# ESP32_Schematic_Sheet.net
KiCad netlist of a schematic drawn in Altium Designer
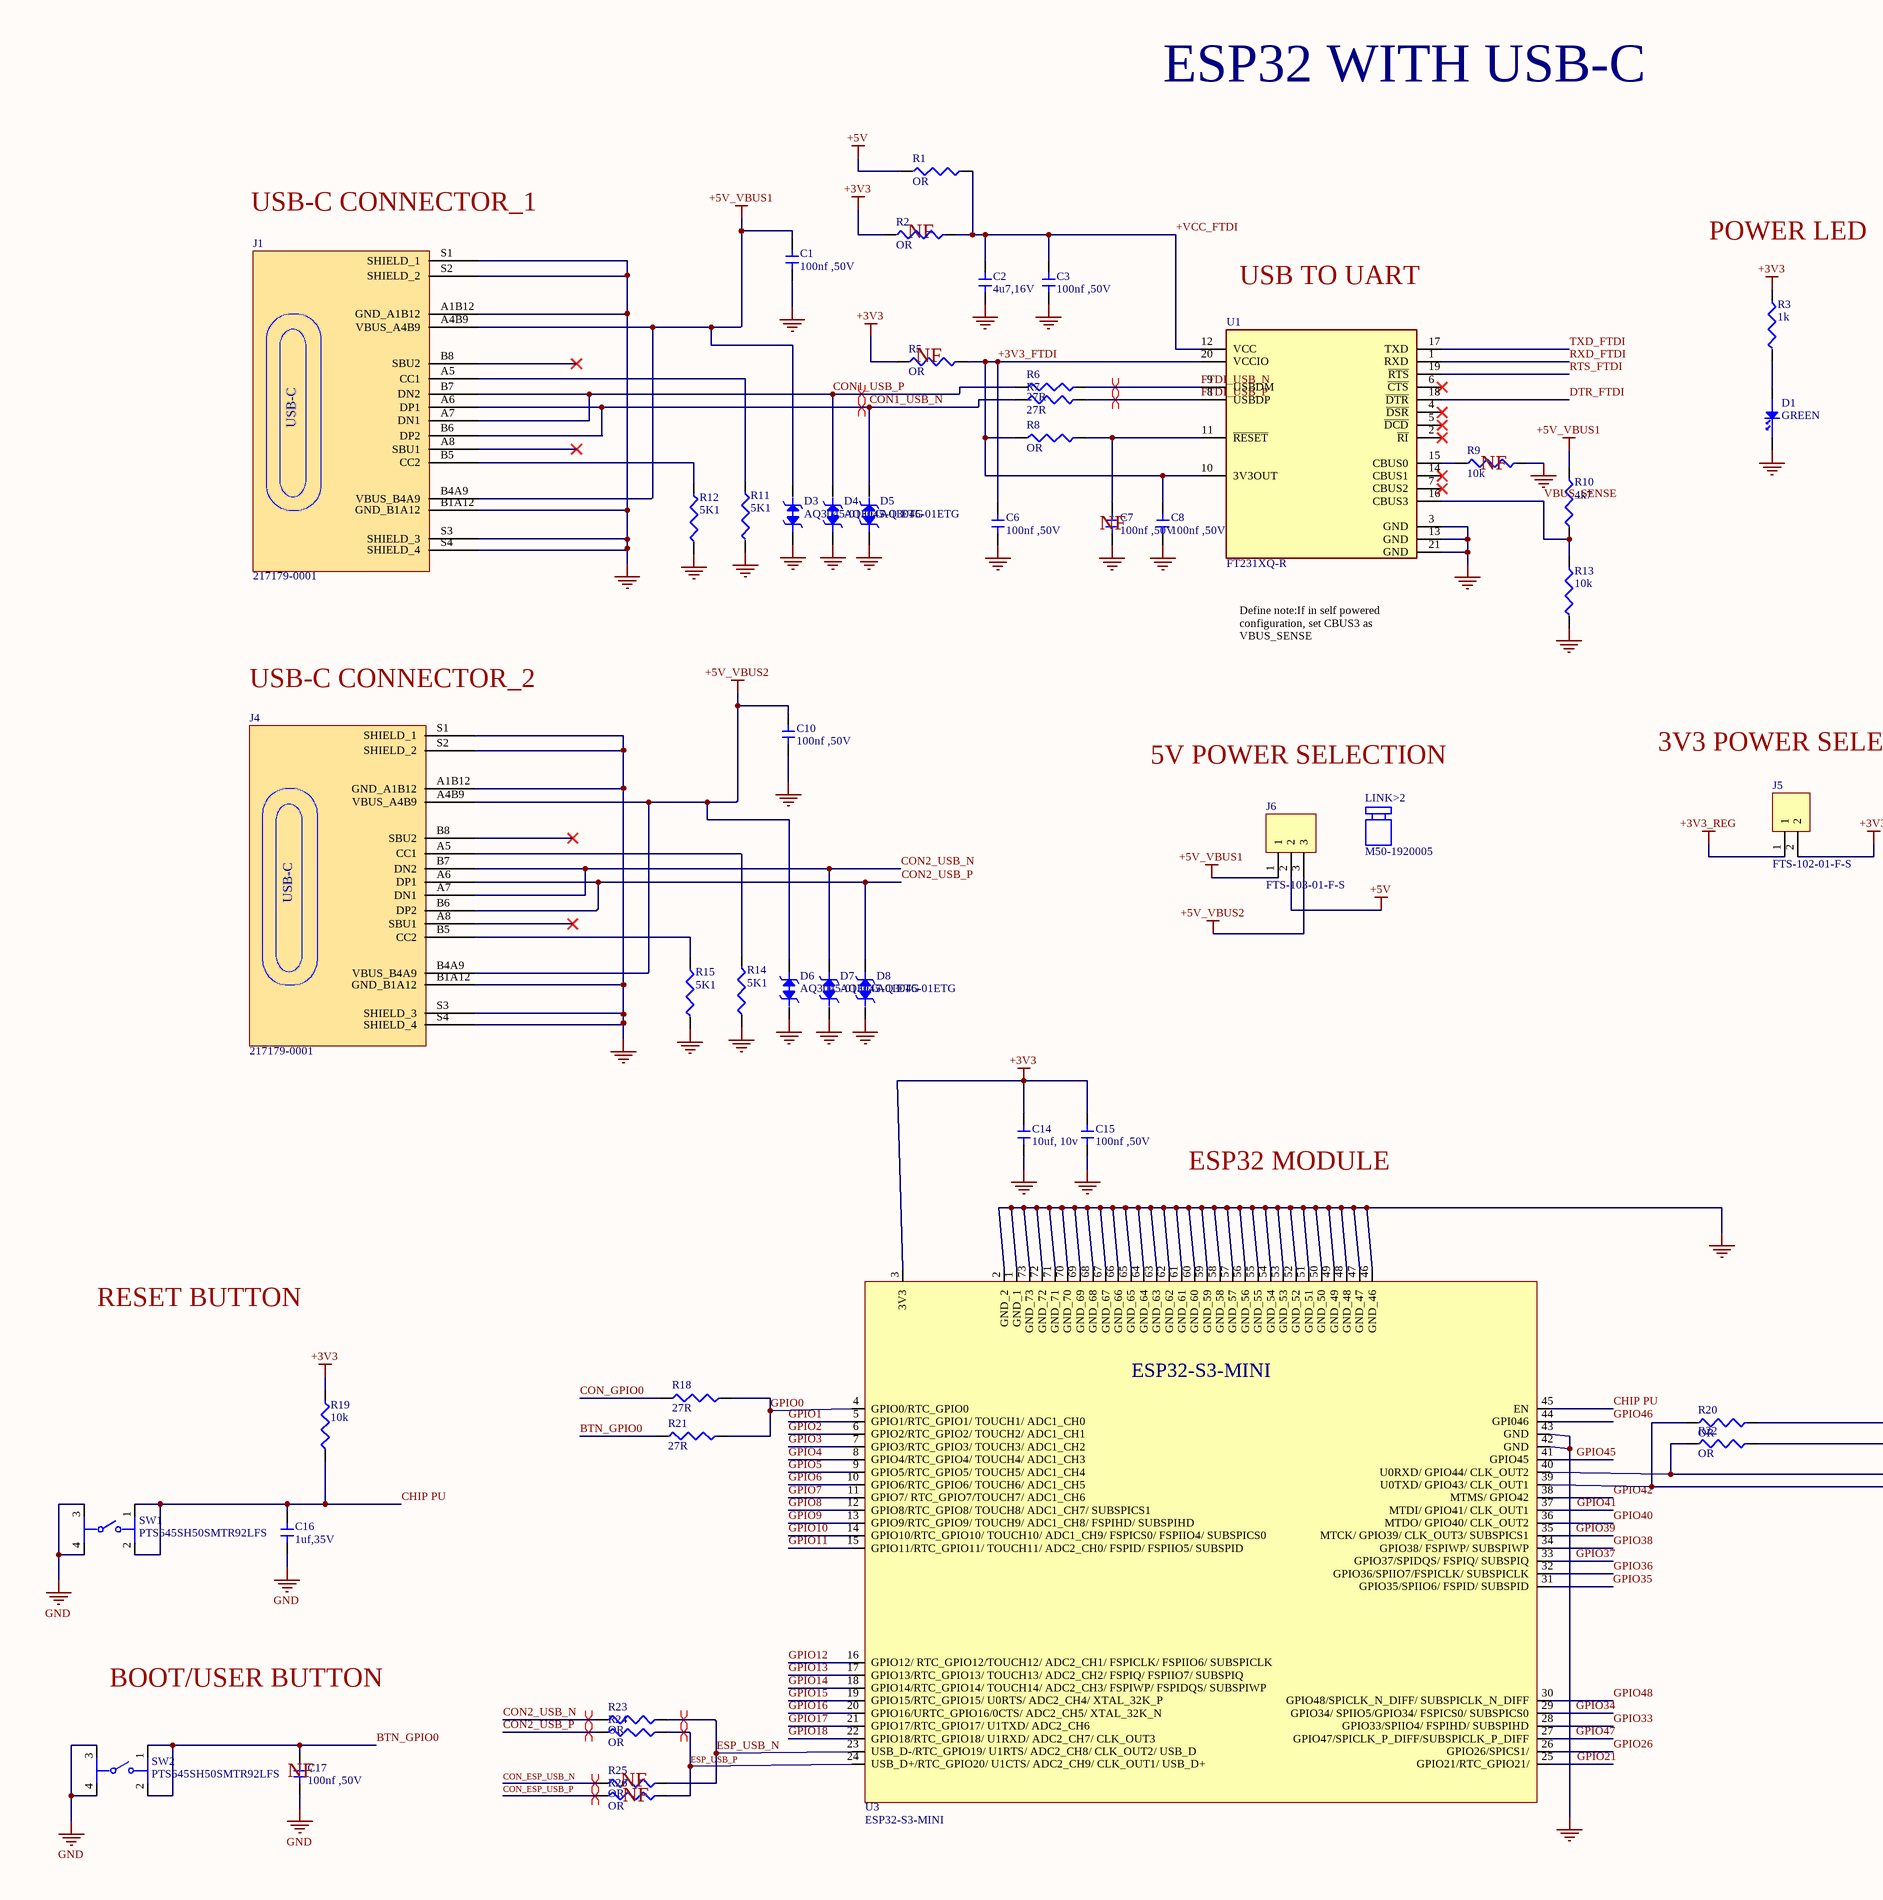
[diagram p0: ESP32 Schematic Sheet.SchDoc, left]
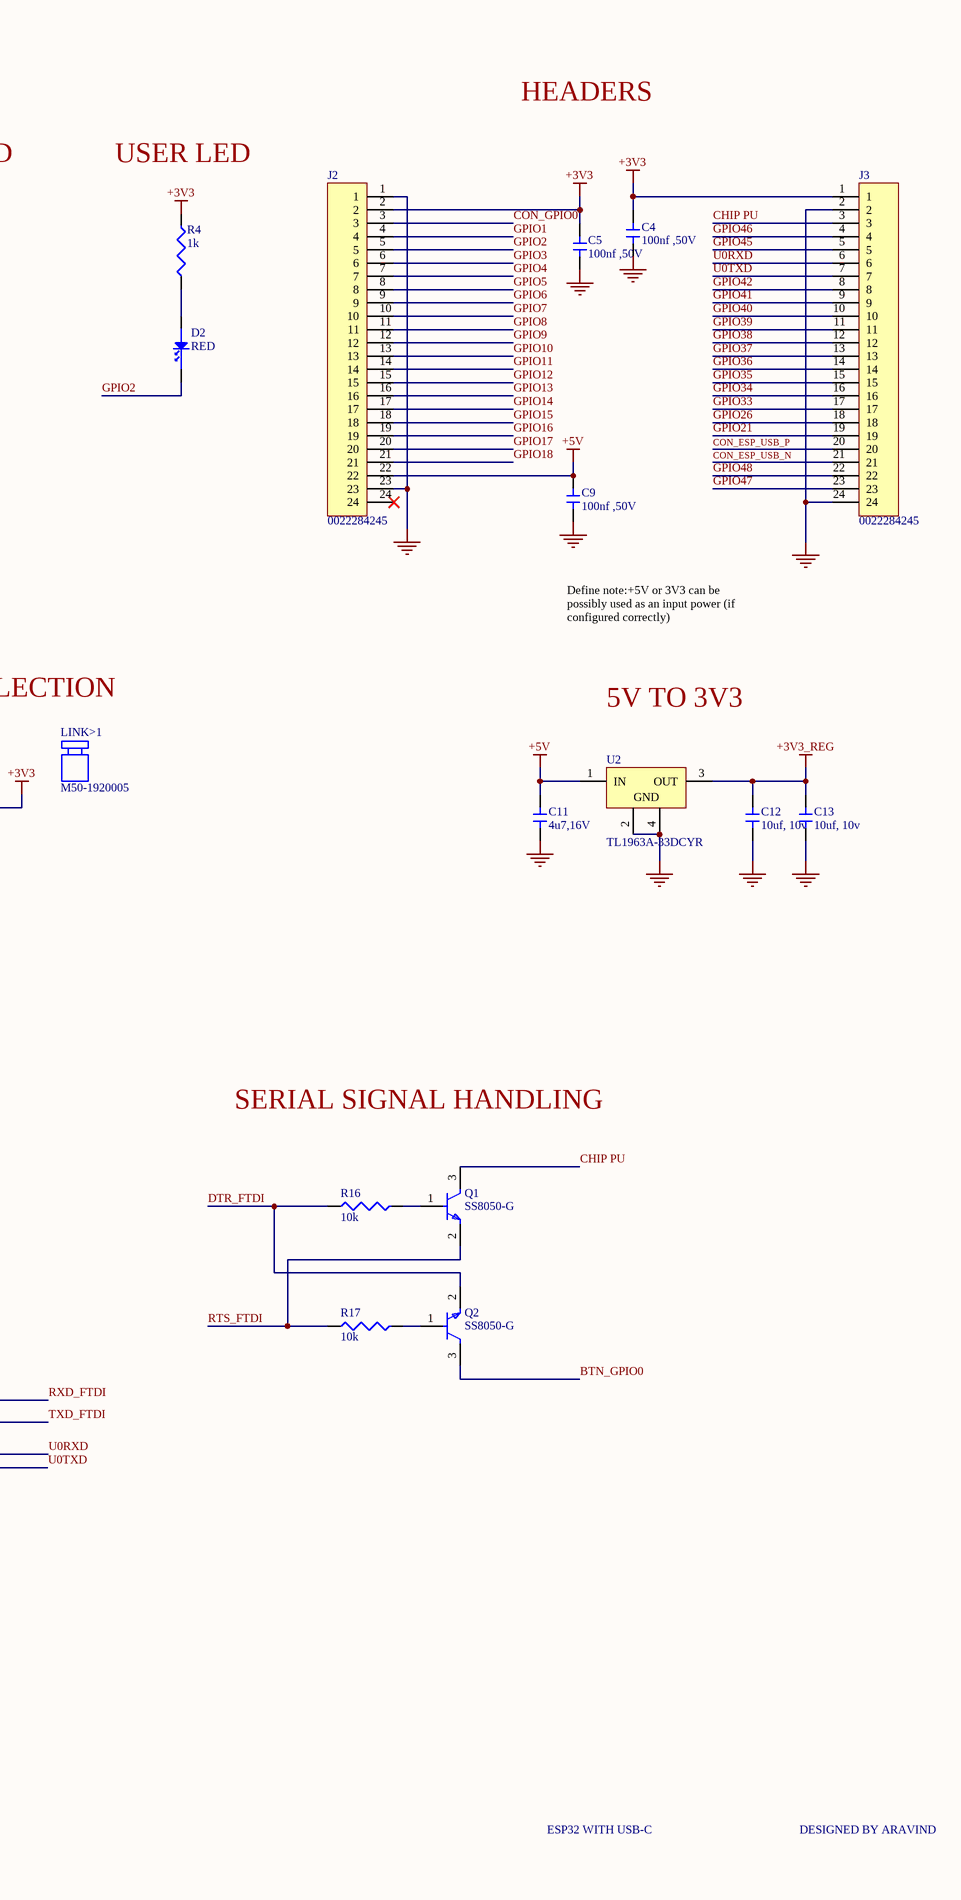
[diagram p1: ESP32 Schematic Sheet.SchDoc, right]

(export (version "E")
  (design (tool "Eeschema 10.0.6"))
  (components
    (comp (ref "C1")
      (value "100nf ,50V")
      (footprint "CAPC1005X55N")
      (description "CAP CER 0.1UF 50V X7R 0402")
      (fields
        (field (name "MANUFACTURER") "Samsung Electro-Mechanics")
        (field (name "MANUFACTURER PART NUMBER") "CL05B104KB5NNNC")
      )
      (libsource (lib "Schlib1") (part "CL05B104KB5NNNC"))
    )
    (comp (ref "C2")
      (value "4u7,16V")
      (footprint "CAPC1005X55N")
      (description "CAP CER 4.7UF 16V X5R 0402")
      (fields
        (field (name "MANUFACTURER") "Samsung Electro-Mechanics")
        (field (name "MANUFACTURER PART NUMBER") "CL05A475MO5NUNC")
      )
      (libsource (lib "Schlib1") (part "CL05A475MO5NUNC"))
    )
    (comp (ref "C3")
      (value "100nf ,50V")
      (footprint "CAPC1005X55N")
      (description "CAP CER 0.1UF 50V X7R 0402")
      (fields
        (field (name "MANUFACTURER") "Samsung Electro-Mechanics")
        (field (name "MANUFACTURER PART NUMBER") "CL05B104KB5NNNC")
      )
      (libsource (lib "Schlib1") (part "CL05B104KB5NNNC"))
    )
    (comp (ref "C4")
      (value "100nf ,50V")
      (footprint "CAPC1005X55N")
      (description "CAP CER 0.1UF 50V X7R 0402")
      (fields
        (field (name "MANUFACTURER") "Samsung Electro-Mechanics")
        (field (name "MANUFACTURER PART NUMBER") "CL05B104KB5NNNC")
      )
      (libsource (lib "Schlib1") (part "CL05B104KB5NNNC"))
    )
    (comp (ref "C5")
      (value "100nf ,50V")
      (footprint "CAPC1005X55N")
      (description "CAP CER 0.1UF 50V X7R 0402")
      (fields
        (field (name "MANUFACTURER") "Samsung Electro-Mechanics")
        (field (name "MANUFACTURER PART NUMBER") "CL05B104KB5NNNC")
      )
      (libsource (lib "Schlib1") (part "CL05B104KB5NNNC"))
    )
    (comp (ref "C6")
      (value "100nf ,50V")
      (footprint "CAPC1005X55N")
      (description "CAP CER 0.1UF 50V X7R 0402")
      (fields
        (field (name "MANUFACTURER") "Samsung Electro-Mechanics")
        (field (name "MANUFACTURER PART NUMBER") "CL05B104KB5NNNC")
      )
      (libsource (lib "Schlib1") (part "CL05B104KB5NNNC"))
    )
    (comp (ref "C7")
      (value "100nf ,50V")
      (footprint "CAPC1005X55N")
      (description "CAP CER 0.1UF 50V X7R 0402")
      (fields
        (field (name "MANUFACTURER") "Samsung Electro-Mechanics")
        (field (name "MANUFACTURER PART NUMBER") "CL05B104KB5NNNC")
      )
      (libsource (lib "Schlib1") (part "CL05B104KB5NNNC"))
    )
    (comp (ref "C8")
      (value "100nf ,50V")
      (footprint "CAPC1005X55N")
      (description "CAP CER 0.1UF 50V X7R 0402")
      (fields
        (field (name "MANUFACTURER") "Samsung Electro-Mechanics")
        (field (name "MANUFACTURER PART NUMBER") "CL05B104KB5NNNC")
      )
      (libsource (lib "Schlib1") (part "CL05B104KB5NNNC"))
    )
    (comp (ref "C9")
      (value "100nf ,50V")
      (footprint "CAPC1005X55N")
      (description "CAP CER 0.1UF 50V X7R 0402")
      (fields
        (field (name "MANUFACTURER") "Samsung Electro-Mechanics")
        (field (name "MANUFACTURER PART NUMBER") "CL05B104KB5NNNC")
      )
      (libsource (lib "Schlib1") (part "CL05B104KB5NNNC"))
    )
    (comp (ref "C10")
      (value "100nf ,50V")
      (footprint "CAPC1005X55N")
      (description "CAP CER 0.1UF 50V X7R 0402")
      (fields
        (field (name "MANUFACTURER") "Samsung Electro-Mechanics")
        (field (name "MANUFACTURER PART NUMBER") "CL05B104KB5NNNC")
      )
      (libsource (lib "Schlib1") (part "CL05B104KB5NNNC"))
    )
    (comp (ref "C11")
      (value "4u7,16V")
      (footprint "CAPC1005X55N")
      (description "CAP CER 4.7UF 16V X5R 0402")
      (fields
        (field (name "MANUFACTURER") "Samsung Electro-Mechanics")
        (field (name "MANUFACTURER PART NUMBER") "CL05A475MO5NUNC")
      )
      (libsource (lib "Schlib1") (part "CL05A475MO5NUNC"))
    )
    (comp (ref "C12")
      (value "10uf, 10v")
      (footprint "CAPC1005X55N")
      (description "CAP CER 10UF 10V X5R 0402")
      (fields
        (field (name "MANUFACTURER") "Samsung Electro-Mechanics")
        (field (name "MANUFACTURER PART NUMBER") "CL05A106MP8NUB8")
      )
      (libsource (lib "Schlib1") (part "CL05A106MP8NUB8"))
    )
    (comp (ref "C13")
      (value "10uf, 10v")
      (footprint "CAPC1005X55N")
      (description "CAP CER 10UF 10V X5R 0402")
      (fields
        (field (name "MANUFACTURER") "Samsung Electro-Mechanics")
        (field (name "MANUFACTURER PART NUMBER") "CL05A106MP8NUB8")
      )
      (libsource (lib "Schlib1") (part "CL05A106MP8NUB8"))
    )
    (comp (ref "C14")
      (value "10uf, 10v")
      (footprint "CAPC1005X55N")
      (description "CAP CER 10UF 10V X5R 0402")
      (fields
        (field (name "MANUFACTURER") "Samsung Electro-Mechanics")
        (field (name "MANUFACTURER PART NUMBER") "CL05A106MP8NUB8")
      )
      (libsource (lib "Schlib1") (part "CL05A106MP8NUB8"))
    )
    (comp (ref "C15")
      (value "100nf ,50V")
      (footprint "CAPC1005X55N")
      (description "CAP CER 0.1UF 50V X7R 0402")
      (fields
        (field (name "MANUFACTURER") "Samsung Electro-Mechanics")
        (field (name "MANUFACTURER PART NUMBER") "CL05B104KB5NNNC")
      )
      (libsource (lib "Schlib1") (part "CL05B104KB5NNNC"))
    )
    (comp (ref "C16")
      (value "1uf,35V")
      (footprint "CAPC1005X55N")
      (description "CAP CER 1UF 35V X5R 0402")
      (fields
        (field (name "MANUFACTURER") "Samsung Electro-Mechanics")
        (field (name "MANUFACTURER PART NUMBER") "CL05A105KL5NRNC")
      )
      (libsource (lib "Schlib1") (part "CL05A105KL5NRNC"))
    )
    (comp (ref "C17")
      (value "100nf ,50V")
      (footprint "CAPC1005X55N")
      (description "CAP CER 0.1UF 50V X7R 0402")
      (fields
        (field (name "MANUFACTURER") "Samsung Electro-Mechanics")
        (field (name "MANUFACTURER PART NUMBER") "CL05B104KB5NNNC")
      )
      (libsource (lib "Schlib1") (part "CL05B104KB5NNNC"))
    )
    (comp (ref "D1")
      (value "GREEN")
      (footprint "LED0402G")
      (description "LED YLW-GRN 0402 SMD")
      (fields
        (field (name "MANUFACTURER") "Vishay")
        (field (name "MANUFACTURER PART NUMBER") "VLMG1500-GS08")
      )
      (libsource (lib "Schlib1") (part "VLMG1500-GS08"))
    )
    (comp (ref "D2")
      (value "RED")
      (footprint "LED0402R")
      (description "LED RED 0402 SMD")
      (fields
        (field (name "MANUFACTURER") "Vishay")
        (field (name "MANUFACTURER PART NUMBER") "VLMS1500-GS08")
      )
      (libsource (lib "Schlib1") (part "VLMS1500-GS08"))
    )
    (comp (ref "D3")
      (value "AQ3045-01ETG")
      (footprint "SOD882")
      (description "TVS DIODE 5.3VWM 12VC SOD882")
      (fields (field (name "MANUFACTURER") "Littelfuse"))
      (libsource (lib "Schlib1") (part "AQ3045-01ETG"))
    )
    (comp (ref "D4")
      (value "AQ3045-01ETG")
      (footprint "SOD882")
      (description "TVS DIODE 5.3VWM 12VC SOD882")
      (fields (field (name "MANUFACTURER") "Littelfuse"))
      (libsource (lib "Schlib1") (part "AQ3045-01ETG"))
    )
    (comp (ref "D5")
      (value "AQ3045-01ETG")
      (footprint "SOD882")
      (description "TVS DIODE 5.3VWM 12VC SOD882")
      (fields (field (name "MANUFACTURER") "Littelfuse"))
      (libsource (lib "Schlib1") (part "AQ3045-01ETG"))
    )
    (comp (ref "D6")
      (value "AQ3045-01ETG")
      (footprint "SOD882")
      (description "TVS DIODE 5.3VWM 12VC SOD882")
      (fields (field (name "MANUFACTURER") "Littelfuse"))
      (libsource (lib "Schlib1") (part "AQ3045-01ETG"))
    )
    (comp (ref "D7")
      (value "AQ3045-01ETG")
      (footprint "SOD882")
      (description "TVS DIODE 5.3VWM 12VC SOD882")
      (fields (field (name "MANUFACTURER") "Littelfuse"))
      (libsource (lib "Schlib1") (part "AQ3045-01ETG"))
    )
    (comp (ref "D8")
      (value "AQ3045-01ETG")
      (footprint "SOD882")
      (description "TVS DIODE 5.3VWM 12VC SOD882")
      (fields (field (name "MANUFACTURER") "Littelfuse"))
      (libsource (lib "Schlib1") (part "AQ3045-01ETG"))
    )
    (comp (ref "J1")
      (value "217179-0001")
      (footprint "FP-2171790001-MFG")
      (description "CONN RCP USB2.0 TYP C 24P SMD RA")
      (fields (field (name "MANUFACTURER") "Molex"))
      (libsource (lib "Schlib1") (part "217179-0001"))
    )
    (comp (ref "J2")
      (value "0022284245")
      (footprint "HDR_1X24_2.54MM")
      (description "CONN HEADER VERT 24POS 2.54MM")
      (fields (field (name "MANUFACTURER") "Molex") (field (name "MANUFACTURER PART NUMBER") "22-28-4245"))
      (libsource (lib "Schlib1") (part "0022284245"))
    )
    (comp (ref "J3")
      (value "0022284245")
      (footprint "HDR_1X24_2.54MM")
      (description "CONN HEADER VERT 24POS 2.54MM")
      (fields (field (name "MANUFACTURER") "Molex") (field (name "MANUFACTURER PART NUMBER") "22-28-4245"))
      (libsource (lib "") (part "0022284245_1"))
    )
    (comp (ref "J4")
      (value "217179-0001")
      (footprint "FP-2171790001-MFG")
      (description "CONN RCP USB2.0 TYP C 24P SMD RA")
      (fields (field (name "MANUFACTURER") "Molex"))
      (libsource (lib "Schlib1") (part "217179-0001"))
    )
    (comp (ref "J5")
      (value "FTS-102-01-F-S")
      (footprint "HDR_1X2_1.27MM")
      (description "CONN HEADER VERT 2POS 1.27MM")
      (fields (field (name "MANUFACTURER") "Samtec"))
      (libsource (lib "FINALSchlib2") (part "FTS-102-01-F-S"))
    )
    (comp (ref "J6")
      (value "FTS-103-01-F-S")
      (footprint "HDR_1X3_1.27MM")
      (description "CONN HEADER VERT 3POS 1.27MM")
      (fields (field (name "MANUFACTURER") "Samtec"))
      (libsource (lib "Schlib1") (part "FTS-103-01-F-S"))
    )
    (comp (ref "LINK>1")
      (value "M50-1920005")
      (description "CONN SHUNT 1.27MM RED")
      (fields (field (name "MANUFACTURER") "Harwin"))
      (libsource (lib "Schlib1") (part "M50-1920005"))
    )
    (comp (ref "LINK>2")
      (value "M50-1920005")
      (description "CONN SHUNT 1.27MM RED")
      (fields (field (name "MANUFACTURER") "Harwin"))
      (libsource (lib "Schlib1") (part "M50-1920005"))
    )
    (comp (ref "Q1")
      (value "SS8050-G")
      (footprint "FP-SS8050-G-IPC_B")
      (description "TRANS NPN 25V 1.5A SOT-23-3")
      (fields (field (name "MANUFACTURER") "Comchip"))
      (libsource (lib "Schlib1") (part "SS8050-G"))
    )
    (comp (ref "Q2")
      (value "SS8050-G")
      (footprint "FP-SS8050-G-IPC_B")
      (description "TRANS NPN 25V 1.5A SOT-23-3")
      (fields (field (name "MANUFACTURER") "Comchip"))
      (libsource (lib "Schlib1") (part "SS8050-G"))
    )
    (comp (ref "R1")
      (value "OR")
      (footprint "RESC1005X37N")
      (description "RES 0 OHM JUMPER 1/16W 0402")
      (fields
        (field (name "MANUFACTURER") "Yageo Group")
        (field (name "MANUFACTURER PART NUMBER") "RC0402JR-070RL")
      )
      (libsource (lib "FINALSchlib2") (part "RC0402JR-070RL"))
    )
    (comp (ref "R2")
      (value "OR")
      (footprint "RESC1005X37N")
      (description "RES 0 OHM JUMPER 1/16W 0402")
      (fields
        (field (name "MANUFACTURER") "Yageo Group")
        (field (name "MANUFACTURER PART NUMBER") "RC0402JR-070RL")
      )
      (libsource (lib "FINALSchlib2") (part "RC0402JR-070RL"))
    )
    (comp (ref "R3")
      (value "1k")
      (footprint "RESC1005X37N")
      (description "RES 1K OHM 1% 1/16W 0402")
      (fields
        (field (name "MANUFACTURER") "Yageo Group")
        (field (name "MANUFACTURER PART NUMBER") "RC0402FR-071KL")
      )
      (libsource (lib "Schlib1") (part "RC0402FR-071KL"))
    )
    (comp (ref "R4")
      (value "1k")
      (footprint "RESC1005X37N")
      (description "RES 1K OHM 1% 1/16W 0402")
      (fields
        (field (name "MANUFACTURER") "Yageo Group")
        (field (name "MANUFACTURER PART NUMBER") "RC0402FR-071KL")
      )
      (libsource (lib "Schlib1") (part "RC0402FR-071KL"))
    )
    (comp (ref "R5")
      (value "OR")
      (footprint "RESC1005X37N")
      (description "RES 0 OHM JUMPER 1/16W 0402")
      (fields
        (field (name "MANUFACTURER") "TE Connectivity")
        (field (name "MANUFACTURER PART NUMBER") "CRG0402ZR")
      )
      (libsource (lib "Schlib1") (part "CRG0402ZR"))
    )
    (comp (ref "R6")
      (value "27R")
      (footprint "RESC1005X37N")
      (description "RES 27 OHM 1% 1/16W 0402")
      (fields
        (field (name "MANUFACTURER") "Yageo Group")
        (field (name "MANUFACTURER PART NUMBER") "RC0402FR-0727RL")
      )
      (libsource (lib "Schlib1") (part "RC0402FR-0727RL"))
    )
    (comp (ref "R7")
      (value "27R")
      (footprint "RESC1005X37N")
      (description "RES 27 OHM 1% 1/16W 0402")
      (fields
        (field (name "MANUFACTURER") "Yageo Group")
        (field (name "MANUFACTURER PART NUMBER") "RC0402FR-0727RL")
      )
      (libsource (lib "Schlib1") (part "RC0402FR-0727RL"))
    )
    (comp (ref "R8")
      (value "OR")
      (footprint "RESC1005X37N")
      (description "RES 0 OHM JUMPER 1/16W 0402")
      (fields
        (field (name "MANUFACTURER") "Yageo Group")
        (field (name "MANUFACTURER PART NUMBER") "RC0402JR-070RL")
      )
      (libsource (lib "FINALSchlib2") (part "RC0402JR-070RL"))
    )
    (comp (ref "R9")
      (value "10k")
      (footprint "RESC1005X37N")
      (description "RES SMD 10K OHM 1% 1/16W 0402")
      (fields
        (field (name "MANUFACTURER") "Yageo Group")
        (field (name "MANUFACTURER PART NUMBER") "AC0402FR-0710KL")
      )
      (libsource (lib "Schlib2") (part "AC0402FR-0710KL"))
    )
    (comp (ref "R10")
      (value "4k7")
      (footprint "RESC1005X37N")
      (description "RES 4.7K OHM 1% 1/16W 0402")
      (fields
        (field (name "MANUFACTURER") "Yageo Group")
        (field (name "MANUFACTURER PART NUMBER") "RC0402FR-074K7L")
      )
      (libsource (lib "Schlib1") (part "RC0402FR-074K7L"))
    )
    (comp (ref "R11")
      (value "5K1")
      (footprint "RESC1005X37N")
      (description "RES SMD 5.1K OHM 1% 1/16W 0402")
      (fields
        (field (name "MANUFACTURER") "Yageo Group")
        (field (name "MANUFACTURER PART NUMBER") "AC0402FR-075K1L")
      )
      (libsource (lib "Schlib1") (part "AC0402FR-075K1L"))
    )
    (comp (ref "R12")
      (value "5K1")
      (footprint "RESC1005X37N")
      (description "RES SMD 5.1K OHM 1% 1/16W 0402")
      (fields
        (field (name "MANUFACTURER") "Yageo Group")
        (field (name "MANUFACTURER PART NUMBER") "AC0402FR-075K1L")
      )
      (libsource (lib "Schlib1") (part "AC0402FR-075K1L"))
    )
    (comp (ref "R13")
      (value "10k")
      (footprint "RESC1005X37N")
      (description "RES SMD 10K OHM 1% 1/16W 0402")
      (fields
        (field (name "MANUFACTURER") "Yageo Group")
        (field (name "MANUFACTURER PART NUMBER") "AC0402FR-0710KL")
      )
      (libsource (lib "Schlib2") (part "AC0402FR-0710KL"))
    )
    (comp (ref "R14")
      (value "5K1")
      (footprint "RESC1005X37N")
      (description "RES SMD 5.1K OHM 1% 1/16W 0402")
      (fields
        (field (name "MANUFACTURER") "Yageo Group")
        (field (name "MANUFACTURER PART NUMBER") "AC0402FR-075K1L")
      )
      (libsource (lib "Schlib1") (part "AC0402FR-075K1L"))
    )
    (comp (ref "R15")
      (value "5K1")
      (footprint "RESC1005X37N")
      (description "RES SMD 5.1K OHM 1% 1/16W 0402")
      (fields
        (field (name "MANUFACTURER") "Yageo Group")
        (field (name "MANUFACTURER PART NUMBER") "AC0402FR-075K1L")
      )
      (libsource (lib "Schlib1") (part "AC0402FR-075K1L"))
    )
    (comp (ref "R16")
      (value "10k")
      (footprint "RESC1005X37N")
      (description "RES SMD 10K OHM 1% 1/16W 0402")
      (fields
        (field (name "MANUFACTURER") "Yageo Group")
        (field (name "MANUFACTURER PART NUMBER") "AC0402FR-0710KL")
      )
      (libsource (lib "Schlib2") (part "AC0402FR-0710KL"))
    )
    (comp (ref "R17")
      (value "10k")
      (footprint "RESC1005X37N")
      (description "RES SMD 10K OHM 1% 1/16W 0402")
      (fields
        (field (name "MANUFACTURER") "Yageo Group")
        (field (name "MANUFACTURER PART NUMBER") "AC0402FR-0710KL")
      )
      (libsource (lib "Schlib2") (part "AC0402FR-0710KL"))
    )
    (comp (ref "R18")
      (value "27R")
      (footprint "RESC1005X37N")
      (description "RES 27 OHM 1% 1/16W 0402")
      (fields
        (field (name "MANUFACTURER") "Yageo Group")
        (field (name "MANUFACTURER PART NUMBER") "RC0402FR-0727RL")
      )
      (libsource (lib "Schlib1") (part "RC0402FR-0727RL"))
    )
    (comp (ref "R19")
      (value "10k")
      (footprint "RESC1005X37N")
      (description "RES SMD 10K OHM 1% 1/16W 0402")
      (fields
        (field (name "MANUFACTURER") "Yageo Group")
        (field (name "MANUFACTURER PART NUMBER") "AC0402FR-0710KL")
      )
      (libsource (lib "Schlib2") (part "AC0402FR-0710KL"))
    )
    (comp (ref "R20")
      (value "OR")
      (footprint "RESC1005X37N")
      (description "RES 0 OHM JUMPER 1/16W 0402")
      (fields
        (field (name "MANUFACTURER") "Yageo Group")
        (field (name "MANUFACTURER PART NUMBER") "RC0402JR-070RL")
      )
      (libsource (lib "FINALSchlib2") (part "RC0402JR-070RL"))
    )
    (comp (ref "R21")
      (value "27R")
      (footprint "RESC1005X37N")
      (description "RES 27 OHM 1% 1/16W 0402")
      (fields
        (field (name "MANUFACTURER") "Yageo Group")
        (field (name "MANUFACTURER PART NUMBER") "RC0402FR-0727RL")
      )
      (libsource (lib "Schlib1") (part "RC0402FR-0727RL"))
    )
    (comp (ref "R22")
      (value "OR")
      (footprint "RESC1005X37N")
      (description "RES 0 OHM JUMPER 1/16W 0402")
      (fields
        (field (name "MANUFACTURER") "Yageo Group")
        (field (name "MANUFACTURER PART NUMBER") "RC0402JR-070RL")
      )
      (libsource (lib "FINALSchlib2") (part "RC0402JR-070RL"))
    )
    (comp (ref "R23")
      (value "OR")
      (footprint "RESC1005X37N")
      (description "RES 0 OHM JUMPER 1/16W 0402")
      (fields
        (field (name "MANUFACTURER") "Yageo Group")
        (field (name "MANUFACTURER PART NUMBER") "RC0402JR-070RL")
      )
      (libsource (lib "FINALSchlib2") (part "RC0402JR-070RL"))
    )
    (comp (ref "R24")
      (value "OR")
      (footprint "RESC1005X37N")
      (description "RES 0 OHM JUMPER 1/16W 0402")
      (fields
        (field (name "MANUFACTURER") "Yageo Group")
        (field (name "MANUFACTURER PART NUMBER") "RC0402JR-070RL")
      )
      (libsource (lib "FINALSchlib2") (part "RC0402JR-070RL"))
    )
    (comp (ref "R25")
      (value "OR")
      (footprint "RESC1005X37N")
      (description "RES 0 OHM JUMPER 1/16W 0402")
      (fields
        (field (name "MANUFACTURER") "Yageo Group")
        (field (name "MANUFACTURER PART NUMBER") "RC0402JR-070RL")
      )
      (libsource (lib "FINALSchlib2") (part "RC0402JR-070RL"))
    )
    (comp (ref "R26")
      (value "OR")
      (footprint "RESC1005X37N")
      (description "RES 0 OHM JUMPER 1/16W 0402")
      (fields
        (field (name "MANUFACTURER") "Yageo Group")
        (field (name "MANUFACTURER PART NUMBER") "RC0402JR-070RL")
      )
      (libsource (lib "FINALSchlib2") (part "RC0402JR-070RL"))
    )
    (comp (ref "SW1")
      (value "PTS645SH50SMTR92LFS")
      (footprint "FP-PTS645SH50SMTR92LFS-MFG")
      (description "SWITCH TACTILE SPST-NO 0.05A 12V")
      (fields (field (name "MANUFACTURER") "C&K Components"))
      (libsource (lib "Schlib1") (part "PTS645SH50SMTR92LFS"))
    )
    (comp (ref "SW2")
      (value "PTS645SH50SMTR92LFS")
      (footprint "FP-PTS645SH50SMTR92LFS-MFG")
      (description "SWITCH TACTILE SPST-NO 0.05A 12V")
      (fields (field (name "MANUFACTURER") "C&K Components"))
      (libsource (lib "Schlib1") (part "PTS645SH50SMTR92LFS"))
    )
    (comp (ref "U1")
      (value "FT231XQ-R")
      (footprint "FP-QFN-20-IPC_B")
      (description "IC USB SERIAL FULL UART 20QFN")
      (fields (field (name "MANUFACTURER") "FTDI"))
      (libsource (lib "Schlib1") (part "FT231XQ-R"))
    )
    (comp (ref "U2")
      (value "TL1963A-33DCYR")
      (footprint "DCY0004A_N")
      (description "IC REG LIN 3.3V 1.5A SOT-223-4")
      (fields (field (name "MANUFACTURER") "Texas Instruments"))
      (libsource (lib "Schlib1") (part "TL1963A-33DCYR"))
    )
    (comp (ref "U3")
      (value "ESP32-S3-MINI")
      (footprint "XCVR_ESP32-S3-MINI-1-N8")
      (description "SMD Module ESP32-S3FN8,8 MB SP")
      (libsource (lib "FINALSchlib2") (part "ESP32-S3-MINI"))
    )
  )
  (nets
    (net (code "1") (name "+3V3") (class "Default")
      (node (ref "C14") (pin "2") (pinfunction "2_2") (pintype "passive"))
      (node (ref "C15") (pin "2") (pinfunction "2_2") (pintype "passive"))
      (node (ref "C4") (pin "2") (pinfunction "2_2") (pintype "passive"))
      (node (ref "C5") (pin "2") (pinfunction "2_2") (pintype "passive"))
      (node (ref "J2") (pin "2") (pinfunction "2_2") (pintype "passive"))
      (node (ref "J3") (pin "1") (pinfunction "1_1") (pintype "passive"))
      (node (ref "J5") (pin "2") (pinfunction "2_2") (pintype "passive"))
      (node (ref "R19") (pin "2") (pinfunction "2_2") (pintype "passive"))
      (node (ref "R2") (pin "1") (pinfunction "1_1") (pintype "passive"))
      (node (ref "R3") (pin "2") (pinfunction "2_2") (pintype "passive"))
      (node (ref "R4") (pin "2") (pinfunction "2_2") (pintype "passive"))
      (node (ref "R5") (pin "1") (pinfunction "1_1") (pintype "passive"))
      (node (ref "U3") (pin "3") (pinfunction "3V3_3") (pintype "passive"))
    )
    (net (code "2") (name "+3V3_REG") (class "Default")
      (node (ref "C12") (pin "2") (pinfunction "2_2") (pintype "passive"))
      (node (ref "C13") (pin "2") (pinfunction "2_2") (pintype "passive"))
      (node (ref "J5") (pin "1") (pinfunction "1_1") (pintype "passive"))
      (node (ref "U2") (pin "3") (pinfunction "OUT_3") (pintype "power_in"))
    )
    (net (code "3") (name "+5V") (class "Default")
      (node (ref "C11") (pin "1") (pinfunction "1_1") (pintype "passive"))
      (node (ref "C9") (pin "2") (pinfunction "2_2") (pintype "passive"))
      (node (ref "J2") (pin "22") (pinfunction "22_22") (pintype "passive"))
      (node (ref "J6") (pin "2") (pinfunction "2_2") (pintype "passive"))
      (node (ref "R1") (pin "1") (pinfunction "1_1") (pintype "passive"))
      (node (ref "U2") (pin "1") (pinfunction "IN_1") (pintype "power_in"))
    )
    (net (code "4") (name "+5V_VBUS1") (class "Default")
      (node (ref "C1") (pin "2") (pinfunction "2_2") (pintype "passive"))
      (node (ref "D3") (pin "2") (pinfunction "2_2") (pintype "passive"))
      (node (ref "J1") (pin "A4B9") (pinfunction "VBUS_A4B9_A4B9") (pintype "passive"))
      (node (ref "J1") (pin "B4A9") (pinfunction "VBUS_B4A9_B4A9") (pintype "passive"))
      (node (ref "J6") (pin "1") (pinfunction "1_1") (pintype "passive"))
      (node (ref "R10") (pin "2") (pinfunction "2_2") (pintype "passive"))
    )
    (net (code "5") (name "+5V_VBUS2") (class "Default")
      (node (ref "C10") (pin "2") (pinfunction "2_2") (pintype "passive"))
      (node (ref "D6") (pin "2") (pinfunction "2_2") (pintype "passive"))
      (node (ref "J4") (pin "A4B9") (pinfunction "VBUS_A4B9_A4B9") (pintype "passive"))
      (node (ref "J4") (pin "B4A9") (pinfunction "VBUS_B4A9_B4A9") (pintype "passive"))
      (node (ref "J6") (pin "3") (pinfunction "3_3") (pintype "passive"))
    )
    (net (code "6") (name "/+3V3_FTDI") (class "Default")
      (node (ref "C6") (pin "2") (pinfunction "2_2") (pintype "passive"))
      (node (ref "C8") (pin "2") (pinfunction "2_2") (pintype "passive"))
      (node (ref "R5") (pin "2") (pinfunction "2_2") (pintype "passive"))
      (node (ref "R8") (pin "1") (pinfunction "1_1") (pintype "passive"))
      (node (ref "U1") (pin "10") (pinfunction "3V3OUT_10") (pintype "passive"))
      (node (ref "U1") (pin "20") (pinfunction "VCCIO_20") (pintype "passive"))
    )
    (net (code "7") (name "/+VCC_FTDI") (class "Default")
      (node (ref "C2") (pin "1") (pinfunction "1_1") (pintype "passive"))
      (node (ref "C3") (pin "2") (pinfunction "2_2") (pintype "passive"))
      (node (ref "R1") (pin "2") (pinfunction "2_2") (pintype "passive"))
      (node (ref "R2") (pin "2") (pinfunction "2_2") (pintype "passive"))
      (node (ref "U1") (pin "12") (pinfunction "VCC_12") (pintype "passive"))
    )
    (net (code "8") (name "/BTN_GPIO0") (class "Default")
      (node (ref "C17") (pin "2") (pinfunction "2_2") (pintype "passive"))
      (node (ref "Q2") (pin "3") (pinfunction "C_3") (pintype "passive"))
      (node (ref "R21") (pin "1") (pinfunction "1_1") (pintype "passive"))
      (node (ref "SW2") (pin "1") (pinfunction "1_1") (pintype "passive"))
      (node (ref "SW2") (pin "2") (pinfunction "2_2") (pintype "passive"))
    )
    (net (code "9") (name "/CHIP PU") (class "Default")
      (node (ref "C16") (pin "2") (pinfunction "2_2") (pintype "passive"))
      (node (ref "J3") (pin "3") (pinfunction "3_3") (pintype "passive"))
      (node (ref "Q1") (pin "3") (pinfunction "C_3") (pintype "passive"))
      (node (ref "R19") (pin "1") (pinfunction "1_1") (pintype "passive"))
      (node (ref "SW1") (pin "1") (pinfunction "1_1") (pintype "passive"))
      (node (ref "SW1") (pin "2") (pinfunction "2_2") (pintype "passive"))
      (node (ref "U3") (pin "45") (pinfunction "EN_45") (pintype "passive"))
    )
    (net (code "10") (name "/CON1_USB_N") (class "Default")
      (node (ref "D5") (pin "2") (pinfunction "2_2") (pintype "passive"))
      (node (ref "J1") (pin "A6") (pinfunction "DP1_A6") (pintype "passive"))
      (node (ref "J1") (pin "B6") (pinfunction "DP2_B6") (pintype "passive"))
      (node (ref "R7") (pin "1") (pinfunction "1_1") (pintype "passive"))
    )
    (net (code "11") (name "/CON1_USB_P") (class "Default")
      (node (ref "D4") (pin "2") (pinfunction "2_2") (pintype "passive"))
      (node (ref "J1") (pin "A7") (pinfunction "DN1_A7") (pintype "passive"))
      (node (ref "J1") (pin "B7") (pinfunction "DN2_B7") (pintype "passive"))
      (node (ref "R6") (pin "1") (pinfunction "1_1") (pintype "passive"))
    )
    (net (code "12") (name "/CON2_USB_N") (class "Default")
      (node (ref "D7") (pin "2") (pinfunction "2_2") (pintype "passive"))
      (node (ref "J4") (pin "A7") (pinfunction "DN1_A7") (pintype "passive"))
      (node (ref "J4") (pin "B7") (pinfunction "DN2_B7") (pintype "passive"))
      (node (ref "R23") (pin "1") (pinfunction "1_1") (pintype "passive"))
    )
    (net (code "13") (name "/CON2_USB_P") (class "Default")
      (node (ref "D8") (pin "2") (pinfunction "2_2") (pintype "passive"))
      (node (ref "J4") (pin "A6") (pinfunction "DP1_A6") (pintype "passive"))
      (node (ref "J4") (pin "B6") (pinfunction "DP2_B6") (pintype "passive"))
      (node (ref "R24") (pin "1") (pinfunction "1_1") (pintype "passive"))
    )
    (net (code "14") (name "/CON_ESP_USB_N") (class "Default")
      (node (ref "J3") (pin "21") (pinfunction "21_21") (pintype "passive"))
      (node (ref "R25") (pin "1") (pinfunction "1_1") (pintype "passive"))
    )
    (net (code "15") (name "/CON_ESP_USB_P") (class "Default")
      (node (ref "J3") (pin "20") (pinfunction "20_20") (pintype "passive"))
      (node (ref "R26") (pin "1") (pinfunction "1_1") (pintype "passive"))
    )
    (net (code "16") (name "/CON_GPIO0") (class "Default")
      (node (ref "J2") (pin "3") (pinfunction "3_3") (pintype "passive"))
      (node (ref "R18") (pin "1") (pinfunction "1_1") (pintype "passive"))
    )
    (net (code "17") (name "/DTR_FTDI") (class "Default")
      (node (ref "Q2") (pin "2") (pinfunction "E_2") (pintype "passive"))
      (node (ref "R16") (pin "1") (pinfunction "1_1") (pintype "passive"))
      (node (ref "U1") (pin "18") (pinfunction "~{DTR}_18") (pintype "passive"))
    )
    (net (code "18") (name "/ESP_USB_N") (class "Default")
      (node (ref "R23") (pin "2") (pinfunction "2_2") (pintype "passive"))
      (node (ref "R25") (pin "2") (pinfunction "2_2") (pintype "passive"))
      (node (ref "U3") (pin "23") (pinfunction "USB_D-/RTC_GPIO19/_U1RTS/_ADC2_CH8/_CLK_OUT2/_USB_D_23") (pintype "passive"))
    )
    (net (code "19") (name "/ESP_USB_P") (class "Default")
      (node (ref "R24") (pin "2") (pinfunction "2_2") (pintype "passive"))
      (node (ref "R26") (pin "2") (pinfunction "2_2") (pintype "passive"))
      (node (ref "U3") (pin "24") (pinfunction "USB_D+/RTC_GPIO20/_U1CTS/_ADC2_CH9/_CLK_OUT1/_USB_D+_24") (pintype "passive"))
    )
    (net (code "20") (name "/FTDI_USB_N") (class "Default")
      (node (ref "R6") (pin "2") (pinfunction "2_2") (pintype "passive"))
      (node (ref "U1") (pin "9") (pinfunction "USBDM_9") (pintype "passive"))
    )
    (net (code "21") (name "/FTDI_USB_P") (class "Default")
      (node (ref "R7") (pin "2") (pinfunction "2_2") (pintype "passive"))
      (node (ref "U1") (pin "8") (pinfunction "USBDP_8") (pintype "passive"))
    )
    (net (code "22") (name "/GPIO0") (class "Default")
      (node (ref "R18") (pin "2") (pinfunction "2_2") (pintype "passive"))
      (node (ref "R21") (pin "2") (pinfunction "2_2") (pintype "passive"))
      (node (ref "U3") (pin "4") (pinfunction "GPIO0/RTC_GPIO0_4") (pintype "passive"))
    )
    (net (code "23") (name "/GPIO1") (class "Default")
      (node (ref "J2") (pin "4") (pinfunction "4_4") (pintype "passive"))
      (node (ref "U3") (pin "5") (pinfunction "GPIO1/RTC_GPIO1/_TOUCH1/_ADC1_CH0_5") (pintype "passive"))
    )
    (net (code "24") (name "/GPIO2") (class "Default")
      (node (ref "D2") (pin "1") (pinfunction "1_1") (pintype "passive"))
      (node (ref "J2") (pin "5") (pinfunction "5_5") (pintype "passive"))
      (node (ref "U3") (pin "6") (pinfunction "GPIO2/RTC_GPIO2/_TOUCH2/_ADC1_CH1_6") (pintype "passive"))
    )
    (net (code "25") (name "/GPIO3") (class "Default")
      (node (ref "J2") (pin "6") (pinfunction "6_6") (pintype "passive"))
      (node (ref "U3") (pin "7") (pinfunction "GPIO3/RTC_GPIO3/_TOUCH3/_ADC1_CH2_7") (pintype "passive"))
    )
    (net (code "26") (name "/GPIO4") (class "Default")
      (node (ref "J2") (pin "7") (pinfunction "7_7") (pintype "passive"))
      (node (ref "U3") (pin "8") (pinfunction "GPIO4/RTC_GPIO4/_TOUCH4/_ADC1_CH3_8") (pintype "passive"))
    )
    (net (code "27") (name "/GPIO5") (class "Default")
      (node (ref "J2") (pin "8") (pinfunction "8_8") (pintype "passive"))
      (node (ref "U3") (pin "9") (pinfunction "GPIO5/RTC_GPIO5/_TOUCH5/_ADC1_CH4_9") (pintype "passive"))
    )
    (net (code "28") (name "/GPIO6") (class "Default")
      (node (ref "J2") (pin "9") (pinfunction "9_9") (pintype "passive"))
      (node (ref "U3") (pin "10") (pinfunction "GPIO6/RTC_GPIO6/_TOUCH6/_ADC1_CH5_10") (pintype "passive"))
    )
    (net (code "29") (name "/GPIO7") (class "Default")
      (node (ref "J2") (pin "10") (pinfunction "10_10") (pintype "passive"))
      (node (ref "U3") (pin "11") (pinfunction "GPIO7/_RTC_GPIO7/TOUCH7/_ADC1_CH6_11") (pintype "passive"))
    )
    (net (code "30") (name "/GPIO8") (class "Default")
      (node (ref "J2") (pin "11") (pinfunction "11_11") (pintype "passive"))
      (node (ref "U3") (pin "12") (pinfunction "GPIO8/RTC_GPIO8/_TOUCH8/_ADC1_CH7/_SUBSPICS1_12") (pintype "passive"))
    )
    (net (code "31") (name "/GPIO9") (class "Default")
      (node (ref "J2") (pin "12") (pinfunction "12_12") (pintype "passive"))
      (node (ref "U3") (pin "13") (pinfunction "GPIO9/RTC_GPIO9/_TOUCH9/_ADC1_CH8/_FSPIHD/_SUBSPIHD_13") (pintype "passive"))
    )
    (net (code "32") (name "/GPIO10") (class "Default")
      (node (ref "J2") (pin "13") (pinfunction "13_13") (pintype "passive"))
      (node (ref "U3") (pin "14") (pinfunction "GPIO10/RTC_GPIO10/_TOUCH10/_ADC1_CH9/_FSPICS0/_FSPIIO4/_SUBSPICS0_14") (pintype "passive"))
    )
    (net (code "33") (name "/GPIO11") (class "Default")
      (node (ref "J2") (pin "14") (pinfunction "14_14") (pintype "passive"))
      (node (ref "U3") (pin "15") (pinfunction "GPIO11/RTC_GPIO11/_TOUCH11/_ADC2_CH0/_FSPID/_FSPIIO5/_SUBSPID_15") (pintype "passive"))
    )
    (net (code "34") (name "/GPIO12") (class "Default")
      (node (ref "J2") (pin "15") (pinfunction "15_15") (pintype "passive"))
      (node (ref "U3") (pin "16") (pinfunction "GPIO12/_RTC_GPIO12/TOUCH12/_ADC2_CH1/_FSPICLK/_FSPIIO6/_SUBSPICLK_16") (pintype "passive"))
    )
    (net (code "35") (name "/GPIO13") (class "Default")
      (node (ref "J2") (pin "16") (pinfunction "16_16") (pintype "passive"))
      (node (ref "U3") (pin "17") (pinfunction "GPIO13/RTC_GPIO13/_TOUCH13/_ADC2_CH2/_FSPIQ/_FSPIIO7/_SUBSPIQ_17") (pintype "passive"))
    )
    (net (code "36") (name "/GPIO14") (class "Default")
      (node (ref "J2") (pin "17") (pinfunction "17_17") (pintype "passive"))
      (node (ref "U3") (pin "18") (pinfunction "GPIO14/RTC_GPIO14/_TOUCH14/_ADC2_CH3/_FSPIWP/_FSPIDQS/_SUBSPIWP_18") (pintype "passive"))
    )
    (net (code "37") (name "/GPIO15") (class "Default")
      (node (ref "J2") (pin "18") (pinfunction "18_18") (pintype "passive"))
      (node (ref "U3") (pin "19") (pinfunction "GPIO15/RTC_GPIO15/_U0RTS/_ADC2_CH4/_XTAL_32K_P_19") (pintype "passive"))
    )
    (net (code "38") (name "/GPIO16") (class "Default")
      (node (ref "J2") (pin "19") (pinfunction "19_19") (pintype "passive"))
      (node (ref "U3") (pin "20") (pinfunction "GPIO16/URTC_GPIO16/0CTS/_ADC2_CH5/_XTAL_32K_N_20") (pintype "passive"))
    )
    (net (code "39") (name "/GPIO17") (class "Default")
      (node (ref "J2") (pin "20") (pinfunction "20_20") (pintype "passive"))
      (node (ref "U3") (pin "21") (pinfunction "GPIO17/RTC_GPIO17/_U1TXD/_ADC2_CH6_21") (pintype "passive"))
    )
    (net (code "40") (name "/GPIO18") (class "Default")
      (node (ref "J2") (pin "21") (pinfunction "21_21") (pintype "passive"))
      (node (ref "U3") (pin "22") (pinfunction "GPIO18/RTC_GPIO18/_U1RXD/_ADC2_CH7/_CLK_OUT3_22") (pintype "passive"))
    )
    (net (code "41") (name "/GPIO21") (class "Default")
      (node (ref "J3") (pin "19") (pinfunction "19_19") (pintype "passive"))
      (node (ref "U3") (pin "25") (pinfunction "GPIO21/RTC_GPIO21/_25") (pintype "passive"))
    )
    (net (code "42") (name "/GPIO26") (class "Default")
      (node (ref "J3") (pin "18") (pinfunction "18_18") (pintype "passive"))
      (node (ref "U3") (pin "26") (pinfunction "GPIO26/SPICS1/_26") (pintype "passive"))
    )
    (net (code "43") (name "/GPIO33") (class "Default")
      (node (ref "J3") (pin "17") (pinfunction "17_17") (pintype "passive"))
      (node (ref "U3") (pin "28") (pinfunction "GPIO33/SPIIO4/_FSPIHD/_SUBSPIHD_28") (pintype "passive"))
    )
    (net (code "44") (name "/GPIO34") (class "Default")
      (node (ref "J3") (pin "16") (pinfunction "16_16") (pintype "passive"))
      (node (ref "U3") (pin "29") (pinfunction "GPIO34/_SPIIO5/GPIO34/_FSPICS0/_SUBSPICS0_29") (pintype "passive"))
    )
    (net (code "45") (name "/GPIO35") (class "Default")
      (node (ref "J3") (pin "15") (pinfunction "15_15") (pintype "passive"))
      (node (ref "U3") (pin "31") (pinfunction "GPIO35/SPIIO6/_FSPID/_SUBSPID_31") (pintype "passive"))
    )
    (net (code "46") (name "/GPIO36") (class "Default")
      (node (ref "J3") (pin "14") (pinfunction "14_14") (pintype "passive"))
      (node (ref "U3") (pin "32") (pinfunction "GPIO36/SPIIO7/FSPICLK/_SUBSPICLK_32") (pintype "passive"))
    )
    (net (code "47") (name "/GPIO37") (class "Default")
      (node (ref "J3") (pin "13") (pinfunction "13_13") (pintype "passive"))
      (node (ref "U3") (pin "33") (pinfunction "GPIO37/SPIDQS/_FSPIQ/_SUBSPIQ_33") (pintype "passive"))
    )
    (net (code "48") (name "/GPIO38") (class "Default")
      (node (ref "J3") (pin "12") (pinfunction "12_12") (pintype "passive"))
      (node (ref "U3") (pin "34") (pinfunction "GPIO38/_FSPIWP/_SUBSPIWP_34") (pintype "passive"))
    )
    (net (code "49") (name "/GPIO39") (class "Default")
      (node (ref "J3") (pin "11") (pinfunction "11_11") (pintype "passive"))
      (node (ref "U3") (pin "35") (pinfunction "MTCK/_GPIO39/_CLK_OUT3/_SUBSPICS1_35") (pintype "passive"))
    )
    (net (code "50") (name "/GPIO40") (class "Default")
      (node (ref "J3") (pin "10") (pinfunction "10_10") (pintype "passive"))
      (node (ref "U3") (pin "36") (pinfunction "MTDO/_GPIO40/_CLK_OUT2_36") (pintype "passive"))
    )
    (net (code "51") (name "/GPIO41") (class "Default")
      (node (ref "J3") (pin "9") (pinfunction "9_9") (pintype "passive"))
      (node (ref "U3") (pin "37") (pinfunction "MTDI/_GPIO41/_CLK_OUT1_37") (pintype "passive"))
    )
    (net (code "52") (name "/GPIO42") (class "Default")
      (node (ref "J3") (pin "8") (pinfunction "8_8") (pintype "passive"))
      (node (ref "U3") (pin "38") (pinfunction "MTMS/_GPIO42_38") (pintype "passive"))
    )
    (net (code "53") (name "/GPIO45") (class "Default")
      (node (ref "J3") (pin "5") (pinfunction "5_5") (pintype "passive"))
      (node (ref "U3") (pin "41") (pinfunction "GPIO45_41") (pintype "passive"))
    )
    (net (code "54") (name "/GPIO46") (class "Default")
      (node (ref "J3") (pin "4") (pinfunction "4_4") (pintype "passive"))
      (node (ref "U3") (pin "44") (pinfunction "GPI046_44") (pintype "passive"))
    )
    (net (code "55") (name "/GPIO47") (class "Default")
      (node (ref "J3") (pin "23") (pinfunction "23_23") (pintype "passive"))
      (node (ref "U3") (pin "27") (pinfunction "GPIO47/SPICLK_P_DIFF/SUBSPICLK_P_DIFF_27") (pintype "passive"))
    )
    (net (code "56") (name "/GPIO48") (class "Default")
      (node (ref "J3") (pin "22") (pinfunction "22_22") (pintype "passive"))
      (node (ref "U3") (pin "30") (pinfunction "GPIO48/SPICLK_N_DIFF/_SUBSPICLK_N_DIFF_30") (pintype "passive"))
    )
    (net (code "57") (name "/RTS_FTDI") (class "Default")
      (node (ref "Q1") (pin "2") (pinfunction "E_2") (pintype "passive"))
      (node (ref "R17") (pin "1") (pinfunction "1_1") (pintype "passive"))
      (node (ref "U1") (pin "19") (pinfunction "~{RTS}_19") (pintype "passive"))
    )
    (net (code "58") (name "/RXD_FTDI") (class "Default")
      (node (ref "R20") (pin "2") (pinfunction "2_2") (pintype "passive"))
      (node (ref "U1") (pin "1") (pinfunction "RXD_1") (pintype "passive"))
    )
    (net (code "59") (name "/TXD_FTDI") (class "Default")
      (node (ref "R22") (pin "2") (pinfunction "2_2") (pintype "passive"))
      (node (ref "U1") (pin "17") (pinfunction "TXD_17") (pintype "passive"))
    )
    (net (code "60") (name "/U0RXD") (class "Default")
      (node (ref "J3") (pin "6") (pinfunction "6_6") (pintype "passive"))
      (node (ref "R22") (pin "1") (pinfunction "1_1") (pintype "passive"))
      (node (ref "U3") (pin "40") (pinfunction "U0RXD/_GPIO44/_CLK_OUT2_40") (pintype "passive"))
    )
    (net (code "61") (name "/U0TXD") (class "Default")
      (node (ref "J3") (pin "7") (pinfunction "7_7") (pintype "passive"))
      (node (ref "R20") (pin "1") (pinfunction "1_1") (pintype "passive"))
      (node (ref "U3") (pin "39") (pinfunction "U0TXD/_GPIO43/_CLK_OUT1_39") (pintype "passive"))
    )
    (net (code "62") (name "/VBUS_SENSE") (class "Default")
      (node (ref "R10") (pin "1") (pinfunction "1_1") (pintype "passive"))
      (node (ref "R13") (pin "2") (pinfunction "2_2") (pintype "passive"))
      (node (ref "U1") (pin "16") (pinfunction "CBUS3_16") (pintype "passive"))
    )
    (net (code "63") (name "GND") (class "Default")
      (node (ref "C1") (pin "1") (pinfunction "1_1") (pintype "passive"))
      (node (ref "C10") (pin "1") (pinfunction "1_1") (pintype "passive"))
      (node (ref "C11") (pin "2") (pinfunction "2_2") (pintype "passive"))
      (node (ref "C12") (pin "1") (pinfunction "1_1") (pintype "passive"))
      (node (ref "C13") (pin "1") (pinfunction "1_1") (pintype "passive"))
      (node (ref "C14") (pin "1") (pinfunction "1_1") (pintype "passive"))
      (node (ref "C15") (pin "1") (pinfunction "1_1") (pintype "passive"))
      (node (ref "C16") (pin "1") (pinfunction "1_1") (pintype "passive"))
      (node (ref "C17") (pin "1") (pinfunction "1_1") (pintype "passive"))
      (node (ref "C2") (pin "2") (pinfunction "2_2") (pintype "passive"))
      (node (ref "C3") (pin "1") (pinfunction "1_1") (pintype "passive"))
      (node (ref "C4") (pin "1") (pinfunction "1_1") (pintype "passive"))
      (node (ref "C5") (pin "1") (pinfunction "1_1") (pintype "passive"))
      (node (ref "C6") (pin "1") (pinfunction "1_1") (pintype "passive"))
      (node (ref "C7") (pin "1") (pinfunction "1_1") (pintype "passive"))
      (node (ref "C8") (pin "1") (pinfunction "1_1") (pintype "passive"))
      (node (ref "C9") (pin "1") (pinfunction "1_1") (pintype "passive"))
      (node (ref "D1") (pin "1") (pinfunction "1_1") (pintype "passive"))
      (node (ref "D3") (pin "1") (pinfunction "1_1") (pintype "passive"))
      (node (ref "D4") (pin "1") (pinfunction "1_1") (pintype "passive"))
      (node (ref "D5") (pin "1") (pinfunction "1_1") (pintype "passive"))
      (node (ref "D6") (pin "1") (pinfunction "1_1") (pintype "passive"))
      (node (ref "D7") (pin "1") (pinfunction "1_1") (pintype "passive"))
      (node (ref "D8") (pin "1") (pinfunction "1_1") (pintype "passive"))
      (node (ref "J1") (pin "A1B12") (pinfunction "GND_A1B12_A1B12") (pintype "passive"))
      (node (ref "J1") (pin "B1A12") (pinfunction "GND_B1A12_B1A12") (pintype "passive"))
      (node (ref "J1") (pin "S1") (pinfunction "SHIELD_1_S1") (pintype "passive"))
      (node (ref "J1") (pin "S2") (pinfunction "SHIELD_2_S2") (pintype "passive"))
      (node (ref "J1") (pin "S3") (pinfunction "SHIELD_3_S3") (pintype "passive"))
      (node (ref "J1") (pin "S4") (pinfunction "SHIELD_4_S4") (pintype "passive"))
      (node (ref "J2") (pin "1") (pinfunction "1_1") (pintype "passive"))
      (node (ref "J2") (pin "23") (pinfunction "23_23") (pintype "passive"))
      (node (ref "J3") (pin "2") (pinfunction "2_2") (pintype "passive"))
      (node (ref "J3") (pin "24") (pinfunction "24_24") (pintype "passive"))
      (node (ref "J4") (pin "A1B12") (pinfunction "GND_A1B12_A1B12") (pintype "passive"))
      (node (ref "J4") (pin "B1A12") (pinfunction "GND_B1A12_B1A12") (pintype "passive"))
      (node (ref "J4") (pin "S1") (pinfunction "SHIELD_1_S1") (pintype "passive"))
      (node (ref "J4") (pin "S2") (pinfunction "SHIELD_2_S2") (pintype "passive"))
      (node (ref "J4") (pin "S3") (pinfunction "SHIELD_3_S3") (pintype "passive"))
      (node (ref "J4") (pin "S4") (pinfunction "SHIELD_4_S4") (pintype "passive"))
      (node (ref "R11") (pin "1") (pinfunction "1_1") (pintype "passive"))
      (node (ref "R12") (pin "1") (pinfunction "1_1") (pintype "passive"))
      (node (ref "R13") (pin "1") (pinfunction "1_1") (pintype "passive"))
      (node (ref "R14") (pin "1") (pinfunction "1_1") (pintype "passive"))
      (node (ref "R15") (pin "1") (pinfunction "1_1") (pintype "passive"))
      (node (ref "R9") (pin "2") (pinfunction "2_2") (pintype "passive"))
      (node (ref "SW1") (pin "3") (pinfunction "3_3") (pintype "passive"))
      (node (ref "SW1") (pin "4") (pinfunction "4_4") (pintype "passive"))
      (node (ref "SW2") (pin "3") (pinfunction "3_3") (pintype "passive"))
      (node (ref "SW2") (pin "4") (pinfunction "4_4") (pintype "passive"))
      (node (ref "U1") (pin "13") (pinfunction "GND_13") (pintype "passive"))
      (node (ref "U1") (pin "21") (pinfunction "GND_21") (pintype "passive"))
      (node (ref "U1") (pin "3") (pinfunction "GND_3") (pintype "passive"))
      (node (ref "U2") (pin "2") (pinfunction "GND_2") (pintype "power_in"))
      (node (ref "U2") (pin "4") (pinfunction "GND_4") (pintype "power_in"))
      (node (ref "U3") (pin "1") (pinfunction "GND_1_1") (pintype "passive"))
      (node (ref "U3") (pin "2") (pinfunction "GND_2_2") (pintype "passive"))
      (node (ref "U3") (pin "42") (pinfunction "GND_42") (pintype "passive"))
      (node (ref "U3") (pin "43") (pinfunction "GND_43") (pintype "passive"))
      (node (ref "U3") (pin "46") (pinfunction "GND_46_46") (pintype "passive"))
      (node (ref "U3") (pin "47") (pinfunction "GND_47_47") (pintype "passive"))
      (node (ref "U3") (pin "48") (pinfunction "GND_48_48") (pintype "passive"))
      (node (ref "U3") (pin "49") (pinfunction "GND_49_49") (pintype "passive"))
      (node (ref "U3") (pin "50") (pinfunction "GND_50_50") (pintype "passive"))
      (node (ref "U3") (pin "51") (pinfunction "GND_51_51") (pintype "passive"))
      (node (ref "U3") (pin "52") (pinfunction "GND_52_52") (pintype "passive"))
      (node (ref "U3") (pin "53") (pinfunction "GND_53_53") (pintype "passive"))
      (node (ref "U3") (pin "54") (pinfunction "GND_54_54") (pintype "passive"))
      (node (ref "U3") (pin "55") (pinfunction "GND_55_55") (pintype "passive"))
      (node (ref "U3") (pin "56") (pinfunction "GND_56_56") (pintype "passive"))
      (node (ref "U3") (pin "57") (pinfunction "GND_57_57") (pintype "passive"))
      (node (ref "U3") (pin "58") (pinfunction "GND_58_58") (pintype "passive"))
      (node (ref "U3") (pin "59") (pinfunction "GND_59_59") (pintype "passive"))
      (node (ref "U3") (pin "60") (pinfunction "GND_60_60") (pintype "passive"))
      (node (ref "U3") (pin "61") (pinfunction "GND_61_61") (pintype "passive"))
      (node (ref "U3") (pin "62") (pinfunction "GND_62_62") (pintype "passive"))
      (node (ref "U3") (pin "63") (pinfunction "GND_63_63") (pintype "passive"))
      (node (ref "U3") (pin "64") (pinfunction "GND_64_64") (pintype "passive"))
      (node (ref "U3") (pin "65") (pinfunction "GND_65_65") (pintype "passive"))
      (node (ref "U3") (pin "66") (pinfunction "GND_66_66") (pintype "passive"))
      (node (ref "U3") (pin "67") (pinfunction "GND_67_67") (pintype "passive"))
      (node (ref "U3") (pin "68") (pinfunction "GND_68_68") (pintype "passive"))
      (node (ref "U3") (pin "69") (pinfunction "GND_69_69") (pintype "passive"))
      (node (ref "U3") (pin "70") (pinfunction "GND_70_70") (pintype "passive"))
      (node (ref "U3") (pin "71") (pinfunction "GND_71_71") (pintype "passive"))
      (node (ref "U3") (pin "72") (pinfunction "GND_72_72") (pintype "passive"))
      (node (ref "U3") (pin "73") (pinfunction "GND_73_73") (pintype "passive"))
    )
    (net (code "64") (name "Net-(D1-Pad2)") (class "Default")
      (node (ref "D1") (pin "2") (pinfunction "2_2") (pintype "passive"))
      (node (ref "R3") (pin "1") (pinfunction "1_1") (pintype "passive"))
    )
    (net (code "65") (name "Net-(D2-Pad2)") (class "Default")
      (node (ref "D2") (pin "2") (pinfunction "2_2") (pintype "passive"))
      (node (ref "R4") (pin "1") (pinfunction "1_1") (pintype "passive"))
    )
    (net (code "66") (name "Net-(J1-CC1)") (class "Default")
      (node (ref "J1") (pin "A5") (pinfunction "CC1_A5") (pintype "passive"))
      (node (ref "R11") (pin "2") (pinfunction "2_2") (pintype "passive"))
    )
    (net (code "67") (name "Net-(J1-CC2)") (class "Default")
      (node (ref "J1") (pin "B5") (pinfunction "CC2_B5") (pintype "passive"))
      (node (ref "R12") (pin "2") (pinfunction "2_2") (pintype "passive"))
    )
    (net (code "68") (name "Net-(J4-CC1)") (class "Default")
      (node (ref "J4") (pin "A5") (pinfunction "CC1_A5") (pintype "passive"))
      (node (ref "R14") (pin "2") (pinfunction "2_2") (pintype "passive"))
    )
    (net (code "69") (name "Net-(J4-CC2)") (class "Default")
      (node (ref "J4") (pin "B5") (pinfunction "CC2_B5") (pintype "passive"))
      (node (ref "R15") (pin "2") (pinfunction "2_2") (pintype "passive"))
    )
    (net (code "70") (name "Net-(Q1-B)") (class "Default")
      (node (ref "Q1") (pin "1") (pinfunction "B_1") (pintype "passive"))
      (node (ref "R16") (pin "2") (pinfunction "2_2") (pintype "passive"))
    )
    (net (code "71") (name "Net-(Q2-B)") (class "Default")
      (node (ref "Q2") (pin "1") (pinfunction "B_1") (pintype "passive"))
      (node (ref "R17") (pin "2") (pinfunction "2_2") (pintype "passive"))
    )
    (net (code "72") (name "Net-(U1-CBUS0)") (class "Default")
      (node (ref "R9") (pin "1") (pinfunction "1_1") (pintype "passive"))
      (node (ref "U1") (pin "15") (pinfunction "CBUS0_15") (pintype "passive"))
    )
    (net (code "73") (name "Net-(U1-~{RESET})") (class "Default")
      (node (ref "C7") (pin "2") (pinfunction "2_2") (pintype "passive"))
      (node (ref "R8") (pin "2") (pinfunction "2_2") (pintype "passive"))
      (node (ref "U1") (pin "11") (pinfunction "~{RESET}_11") (pintype "passive"))
    )
    (net (code "74") (name "unconnected-(J1-SBU1-PadA8)") (class "Default")
      (node (ref "J1") (pin "A8") (pinfunction "SBU1_A8") (pintype "passive+no_connect"))
    )
    (net (code "75") (name "unconnected-(J1-SBU2-PadB8)") (class "Default")
      (node (ref "J1") (pin "B8") (pinfunction "SBU2_B8") (pintype "passive+no_connect"))
    )
    (net (code "76") (name "unconnected-(J2-Pad24)") (class "Default")
      (node (ref "J2") (pin "24") (pinfunction "24_24") (pintype "passive+no_connect"))
    )
    (net (code "77") (name "unconnected-(J4-SBU1-PadA8)") (class "Default")
      (node (ref "J4") (pin "A8") (pinfunction "SBU1_A8") (pintype "passive+no_connect"))
    )
    (net (code "78") (name "unconnected-(J4-SBU2-PadB8)") (class "Default")
      (node (ref "J4") (pin "B8") (pinfunction "SBU2_B8") (pintype "passive+no_connect"))
    )
    (net (code "79") (name "unconnected-(U1-CBUS1-Pad14)") (class "Default")
      (node (ref "U1") (pin "14") (pinfunction "CBUS1_14") (pintype "passive+no_connect"))
    )
    (net (code "80") (name "unconnected-(U1-CBUS2-Pad7)") (class "Default")
      (node (ref "U1") (pin "7") (pinfunction "CBUS2_7") (pintype "passive+no_connect"))
    )
    (net (code "81") (name "unconnected-(U1-~{CTS}-Pad6)") (class "Default")
      (node (ref "U1") (pin "6") (pinfunction "~{CTS}_6") (pintype "passive+no_connect"))
    )
    (net (code "82") (name "unconnected-(U1-~{DCD}-Pad5)") (class "Default")
      (node (ref "U1") (pin "5") (pinfunction "~{DCD}_5") (pintype "passive+no_connect"))
    )
    (net (code "83") (name "unconnected-(U1-~{DSR}-Pad4)") (class "Default")
      (node (ref "U1") (pin "4") (pinfunction "~{DSR}_4") (pintype "passive+no_connect"))
    )
    (net (code "84") (name "unconnected-(U1-~{RI}-Pad2)") (class "Default")
      (node (ref "U1") (pin "2") (pinfunction "~{RI}_2") (pintype "passive+no_connect"))
    )
  )
)
